# power-v2v5.net
KiCad netlist of a schematic drawn in Altium Designer
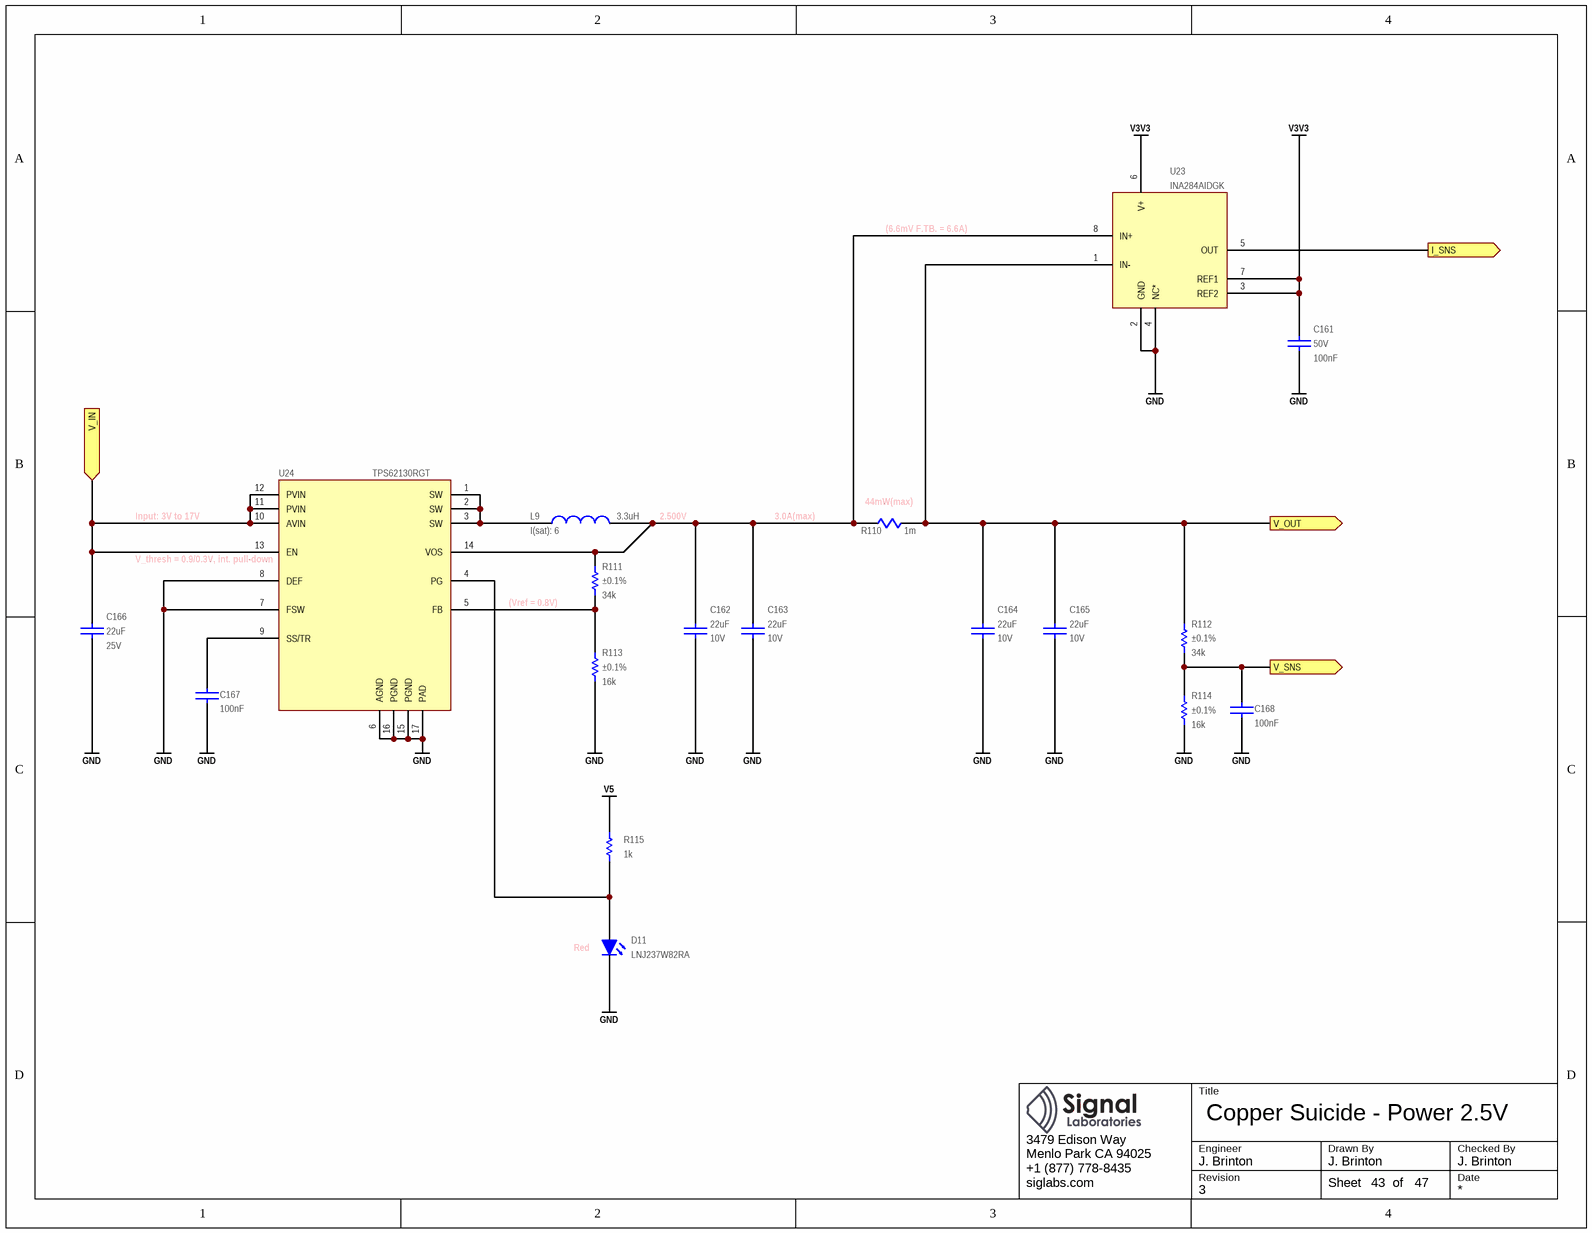
[diagram p0: power-v2v5.SchDoc]

(export (version "E")
  (design (tool "Eeschema 10.0.6"))
  (components
    (comp (ref "C161")
      (value "100nF")
      (footprint "CAPC100X50X55L25N")
      (description "Ceramic Capacitor 100nF ±10% 50V X7R 0402")
      (fields
        (field (name "MANUFACTURER") "Murata")
        (field (name "TOLERANCE") "±10%")
        (field (name "VOLTAGE") "50V")
      )
      (libsource (lib "") (part "CAP_1"))
    )
    (comp (ref "C162")
      (value "22uF")
      (footprint "CAPC200X125X145L45N")
      (description "Ceramic Capacitor 22uF ±20% 10V X7S 0805")
      (fields
        (field (name "MANUFACTURER") "TDK")
        (field (name "TOLERANCE") "±20%")
        (field (name "VOLTAGE") "10V")
      )
      (libsource (lib "generic") (part "CAP"))
    )
    (comp (ref "C163")
      (value "22uF")
      (footprint "CAPC200X125X145L45N")
      (description "Ceramic Capacitor 22uF ±20% 10V X7S 0805")
      (fields
        (field (name "MANUFACTURER") "TDK")
        (field (name "TOLERANCE") "±20%")
        (field (name "VOLTAGE") "10V")
      )
      (libsource (lib "generic") (part "CAP"))
    )
    (comp (ref "C164")
      (value "22uF")
      (footprint "CAPC200X125X145L45N")
      (description "Ceramic Capacitor 22uF ±20% 10V X7S 0805")
      (fields
        (field (name "MANUFACTURER") "TDK")
        (field (name "TOLERANCE") "±20%")
        (field (name "VOLTAGE") "10V")
      )
      (libsource (lib "generic") (part "CAP"))
    )
    (comp (ref "C165")
      (value "22uF")
      (footprint "CAPC200X125X145L45N")
      (description "Ceramic Capacitor 22uF ±20% 10V X7S 0805")
      (fields
        (field (name "MANUFACTURER") "TDK")
        (field (name "TOLERANCE") "±20%")
        (field (name "VOLTAGE") "10V")
      )
      (libsource (lib "generic") (part "CAP"))
    )
    (comp (ref "C166")
      (value "22uF")
      (footprint "CAPC320X250X270L50N")
      (description "Ceramic Capacitor 22uF ±10% 25V X7R 1210")
      (fields
        (field (name "MANUFACTURER") "Murata")
        (field (name "TOLERANCE") "±10%")
        (field (name "VOLTAGE") "25V")
      )
      (libsource (lib "") (part "CAP_1"))
    )
    (comp (ref "C167")
      (value "100nF")
      (footprint "CAPC100X50X55L25N")
      (description "Ceramic Capacitor 100nF ±10% 50V X7R 0402")
      (fields (field (name "MANUFACTURER") "Murata") (field (name "TOLERANCE") "±10%"))
      (libsource (lib "generic") (part "CAP"))
    )
    (comp (ref "C168")
      (value "100nF")
      (footprint "CAPC100X50X55L25N")
      (description "Ceramic Capacitor 100nF ±10% 50V X7R 0402")
      (fields (field (name "MANUFACTURER") "Murata") (field (name "TOLERANCE") "±10%"))
      (libsource (lib "generic") (part "CAP"))
    )
    (comp (ref "D11")
      (value "LNJ237W82RA")
      (footprint "0603_LED")
      (description "LED, SMT 0603, Color Red, 5mA, 1.85V")
      (fields (field (name "MANUFACTURER") "Panasonic"))
      (libsource (lib "generic") (part "LED0603RD"))
    )
    (comp (ref "L9")
      (value "3.3uH")
      (footprint "coilcraft:XAL6030")
      (description "Shielded Power Inductor 3.3uH, 6A")
      (fields
        (field (name "MANUFACTURER") "Coilcraft")
        (field (name "I(SAT)") "6")
        (field (name "Comment") "XAL6030-332ME")
      )
      (libsource (lib "generic") (part "INDUCTOR"))
    )
    (comp (ref "R110")
      (value "1m")
      (footprint "RESC3216X80L110N")
      (description "Current Sense Resistor 1mOhm +/-1% SMD 1206")
      (fields (field (name "MANUFACTURER") "Riedon") (field (name "Comment") "CSR1206-0R001F1"))
      (libsource (lib "Kron Library Rev 3") (part "CSR1206-0R001F1"))
    )
    (comp (ref "R111")
      (value "34k")
      (footprint "RESC2012X70N")
      (description "Thin Film Resistor 34k ±0.1% 0.125W 100V 0805")
      (fields
        (field (name "TOLERANCE") "±0.1%")
        (field (name "MANUFACTURER") "Panasonic")
        (field (name "VOLTAGE") "100")
      )
      (libsource (lib "generic") (part "RES"))
    )
    (comp (ref "R112")
      (value "34k")
      (footprint "RESC2012X70N")
      (description "Thin Film Resistor 34k ±0.1% 0.125W 100V 0805")
      (fields
        (field (name "TOLERANCE") "±0.1%")
        (field (name "MANUFACTURER") "Panasonic")
        (field (name "VOLTAGE") "100")
      )
      (libsource (lib "generic") (part "RES"))
    )
    (comp (ref "R113")
      (value "16k")
      (footprint "RESC2012X70N")
      (description "Thin Film Resistor 16k ±0.1% 0.125W 100V 0805")
      (fields
        (field (name "TOLERANCE") "±0.1%")
        (field (name "MANUFACTURER") "Panasonic")
        (field (name "VOLTAGE") "100")
      )
      (libsource (lib "generic") (part "RES"))
    )
    (comp (ref "R114")
      (value "16k")
      (footprint "RESC2012X70N")
      (description "Thin Film Resistor 16k ±0.1% 0.125W 100V 0805")
      (fields
        (field (name "TOLERANCE") "±0.1%")
        (field (name "MANUFACTURER") "Panasonic")
        (field (name "VOLTAGE") "100")
      )
      (libsource (lib "generic") (part "RES"))
    )
    (comp (ref "R115")
      (value "1k")
      (footprint "RESC1005X40N")
      (description "Thick Film Resistor 1k ±1% 0.1W 50V 0402")
      (fields (field (name "MANUFACTURER") "Panasonic") (field (name "TOLERANCE") "±1%"))
      (libsource (lib "generic") (part "RES"))
    )
    (comp (ref "U23")
      (value "INA284AIDGK")
      (footprint "texas_instruments:S-PDSO-G8")
      (description "Bidirectional Current Shunt Monitor")
      (fields (field (name "MANUFACTURER") "Texas Instruments"))
      (libsource (lib "ti") (part "INA283AIDGK"))
    )
    (comp (ref "U24")
      (value "TPS62130RGT")
      (footprint "S-PQFP-8N")
      (description "3-17V 3A Step-Down Converter VQFN")
      (fields (field (name "MANUFACTURER") "Texas Instruments"))
      (libsource (lib "ti") (part "TPS62130RGT"))
    )
  )
  (nets
    (net (code "1") (name "/I_SNS") (class "Default")
      (node (ref "U23") (pin "5") (pinfunction "OUT_5") (pintype "passive"))
    )
    (net (code "2") (name "/V_IN") (class "Default")
      (node (ref "C166") (pin "2") (pinfunction "2_2") (pintype "passive"))
      (node (ref "U24") (pin "10") (pinfunction "AVIN_10") (pintype "passive"))
      (node (ref "U24") (pin "11") (pinfunction "PVIN_11") (pintype "passive"))
      (node (ref "U24") (pin "12") (pinfunction "PVIN_12") (pintype "passive"))
      (node (ref "U24") (pin "13") (pinfunction "EN_13") (pintype "passive"))
    )
    (net (code "3") (name "/V_OUT") (class "Default")
      (node (ref "C164") (pin "2") (pinfunction "2_2") (pintype "passive"))
      (node (ref "C165") (pin "2") (pinfunction "2_2") (pintype "passive"))
      (node (ref "R110") (pin "2") (pintype "passive"))
      (node (ref "R112") (pin "2") (pinfunction "2_2") (pintype "passive"))
      (node (ref "U23") (pin "1") (pinfunction "IN-_1") (pintype "passive"))
    )
    (net (code "4") (name "/V_SNS") (class "Default")
      (node (ref "C168") (pin "2") (pinfunction "2_2") (pintype "passive"))
      (node (ref "R112") (pin "1") (pinfunction "1_1") (pintype "passive"))
      (node (ref "R114") (pin "2") (pinfunction "2_2") (pintype "passive"))
    )
    (net (code "5") (name "GND") (class "Default")
      (node (ref "C161") (pin "1") (pinfunction "1_1") (pintype "passive"))
      (node (ref "C162") (pin "1") (pinfunction "1_1") (pintype "passive"))
      (node (ref "C163") (pin "1") (pinfunction "1_1") (pintype "passive"))
      (node (ref "C164") (pin "1") (pinfunction "1_1") (pintype "passive"))
      (node (ref "C165") (pin "1") (pinfunction "1_1") (pintype "passive"))
      (node (ref "C166") (pin "1") (pinfunction "1_1") (pintype "passive"))
      (node (ref "C167") (pin "1") (pinfunction "1_1") (pintype "passive"))
      (node (ref "C168") (pin "1") (pinfunction "1_1") (pintype "passive"))
      (node (ref "D11") (pin "2") (pinfunction "K_2") (pintype "passive"))
      (node (ref "R113") (pin "1") (pinfunction "1_1") (pintype "passive"))
      (node (ref "R114") (pin "1") (pinfunction "1_1") (pintype "passive"))
      (node (ref "U23") (pin "2") (pinfunction "GND_2") (pintype "passive"))
      (node (ref "U23") (pin "4") (pinfunction "NC*_4") (pintype "passive"))
      (node (ref "U24") (pin "15") (pinfunction "PGND_15") (pintype "passive"))
      (node (ref "U24") (pin "16") (pinfunction "PGND_16") (pintype "passive"))
      (node (ref "U24") (pin "17") (pinfunction "PAD_17") (pintype "passive"))
      (node (ref "U24") (pin "6") (pinfunction "AGND_6") (pintype "passive"))
      (node (ref "U24") (pin "7") (pinfunction "FSW_7") (pintype "passive"))
      (node (ref "U24") (pin "8") (pinfunction "DEF_8") (pintype "passive"))
    )
    (net (code "6") (name "Net-(D11-A)") (class "Default")
      (node (ref "D11") (pin "1") (pinfunction "A_1") (pintype "passive"))
      (node (ref "R115") (pin "1") (pinfunction "1_1") (pintype "passive"))
      (node (ref "U24") (pin "4") (pinfunction "PG_4") (pintype "passive"))
    )
    (net (code "7") (name "Net-(L9-Pad1)") (class "Default")
      (node (ref "L9") (pin "1") (pinfunction "1_1") (pintype "passive"))
      (node (ref "U24") (pin "1") (pinfunction "SW_1") (pintype "passive"))
      (node (ref "U24") (pin "2") (pinfunction "SW_2") (pintype "passive"))
      (node (ref "U24") (pin "3") (pinfunction "SW_3") (pintype "passive"))
    )
    (net (code "8") (name "Net-(U23-IN+)") (class "Default")
      (node (ref "C162") (pin "2") (pinfunction "2_2") (pintype "passive"))
      (node (ref "C163") (pin "2") (pinfunction "2_2") (pintype "passive"))
      (node (ref "L9") (pin "2") (pinfunction "2_2") (pintype "passive"))
      (node (ref "R110") (pin "1") (pintype "passive"))
      (node (ref "R111") (pin "2") (pinfunction "2_2") (pintype "passive"))
      (node (ref "U23") (pin "8") (pinfunction "IN+_8") (pintype "passive"))
      (node (ref "U24") (pin "14") (pinfunction "VOS_14") (pintype "passive"))
    )
    (net (code "9") (name "Net-(U24-FB)") (class "Default")
      (node (ref "R111") (pin "1") (pinfunction "1_1") (pintype "passive"))
      (node (ref "R113") (pin "2") (pinfunction "2_2") (pintype "passive"))
      (node (ref "U24") (pin "5") (pinfunction "FB_5") (pintype "passive"))
    )
    (net (code "10") (name "Net-(U24-SS{slash}TR)") (class "Default")
      (node (ref "C167") (pin "2") (pinfunction "2_2") (pintype "passive"))
      (node (ref "U24") (pin "9") (pinfunction "SS/TR_9") (pintype "passive"))
    )
    (net (code "11") (name "V3V3") (class "Default")
      (node (ref "C161") (pin "2") (pinfunction "2_2") (pintype "passive"))
      (node (ref "U23") (pin "3") (pinfunction "REF2_3") (pintype "passive"))
      (node (ref "U23") (pin "6") (pinfunction "V+_6") (pintype "passive"))
      (node (ref "U23") (pin "7") (pinfunction "REF1_7") (pintype "passive"))
    )
    (net (code "12") (name "V5") (class "Default")
      (node (ref "R115") (pin "2") (pinfunction "2_2") (pintype "passive"))
    )
  )
)
